# teensy-jst_01_1.net
KiCad netlist of a schematic drawn in EAGLE
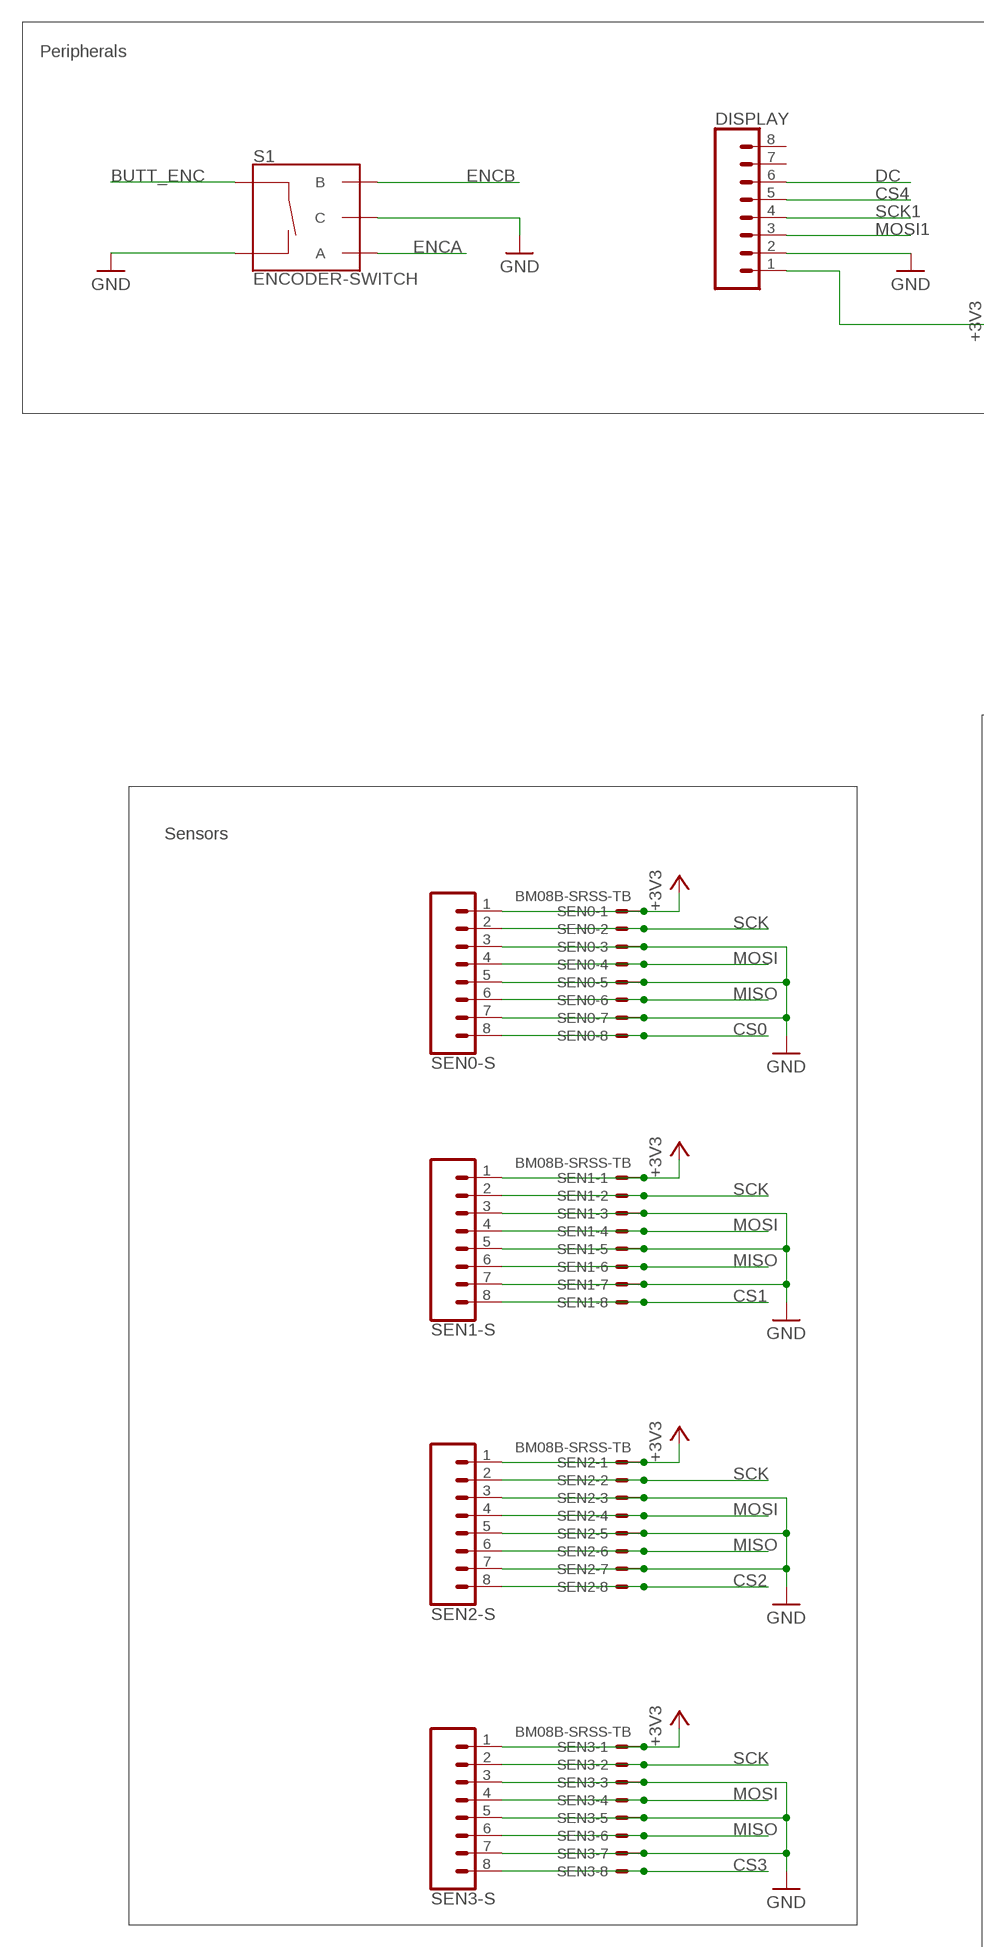
[diagram p0: schematic, sheet 1, part 1 of 2]
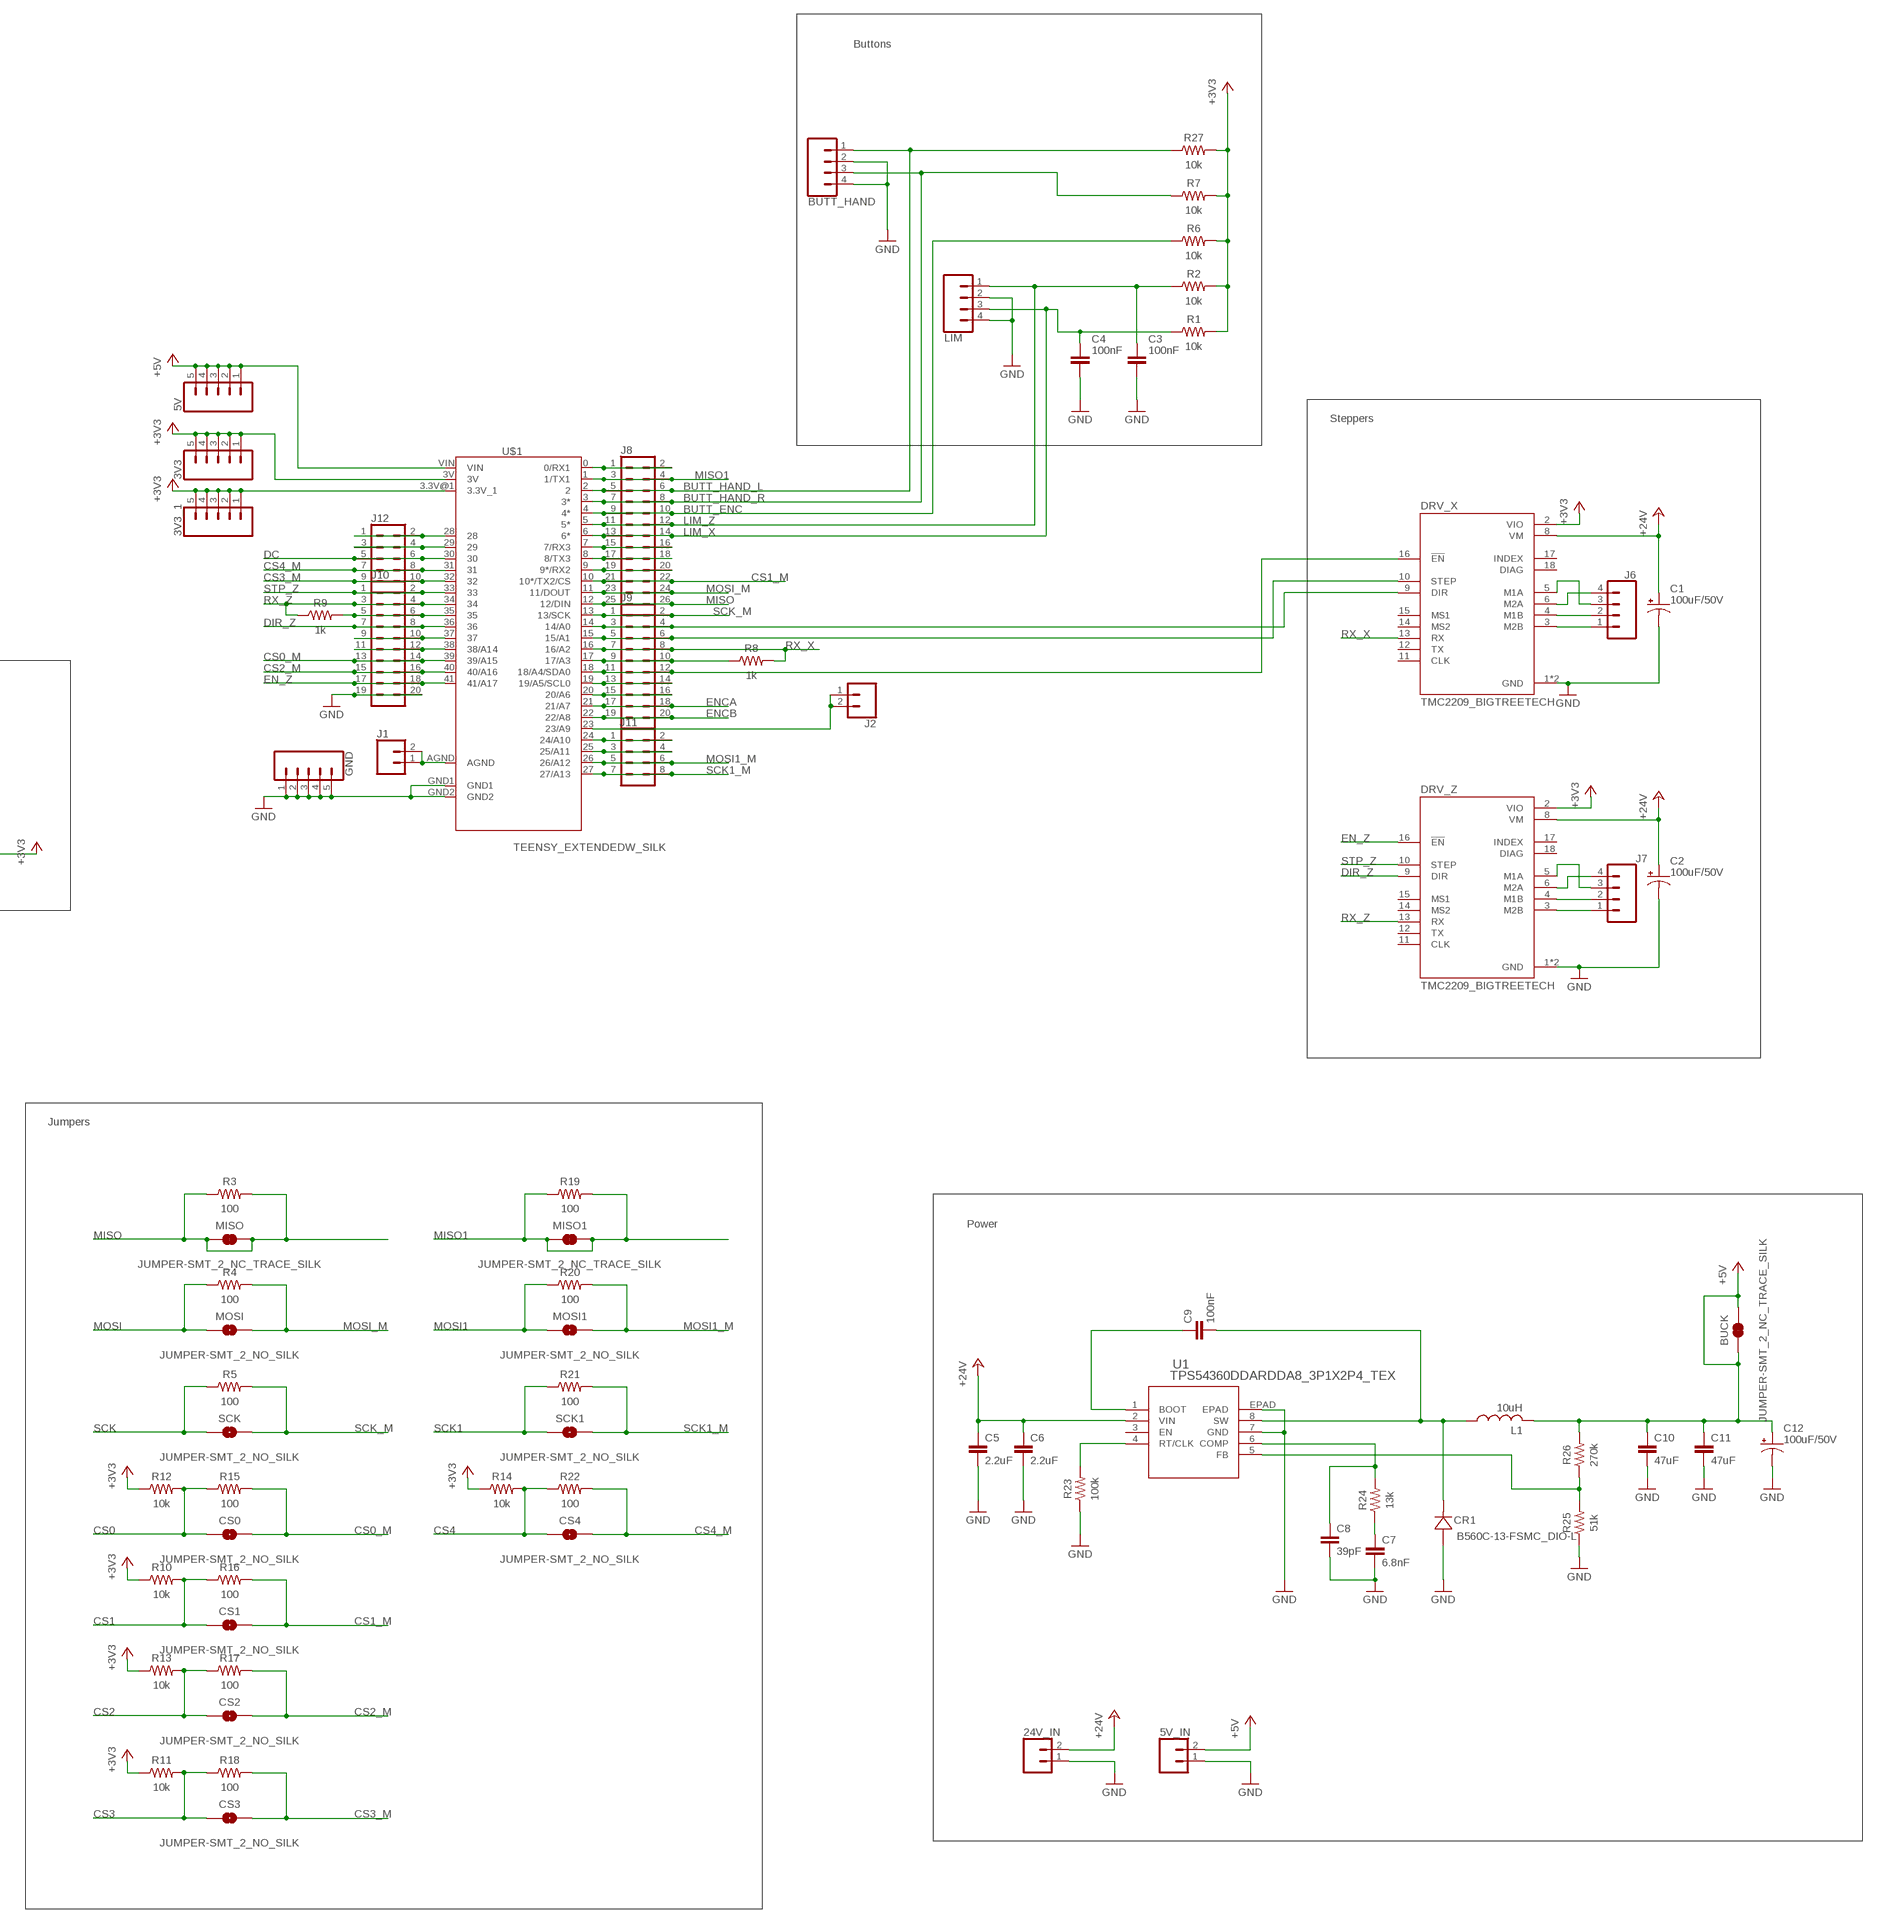
[diagram p1: schematic, sheet 1, part 2 of 2]

(export (version "E")
  (design (tool "Eeschema 10.0.6"))
  (components
    (comp (ref "3V3")
      (value "CONN_05PTH")
      (footprint "eagle-import:1X05")
      (libsource (lib "eagle-import") (part "CONN_05PTH"))
    )
    (comp (ref "3V3_1")
      (value "CONN_05PTH")
      (footprint "eagle-import:1X05")
      (libsource (lib "eagle-import") (part "CONN_05PTH"))
    )
    (comp (ref "5V")
      (value "CONN_05PTH")
      (footprint "eagle-import:1X05")
      (libsource (lib "eagle-import") (part "CONN_05PTH"))
    )
    (comp (ref "5V_IN")
      (value "CONN_025MM")
      (footprint "eagle-import:SCREWTERMINAL-5MM-2")
      (libsource (lib "eagle-import") (part "CONN_025MM"))
    )
    (comp (ref "24V_IN")
      (value "CONN_025MM")
      (footprint "eagle-import:SCREWTERMINAL-5MM-2")
      (libsource (lib "eagle-import") (part "CONN_025MM"))
    )
    (comp (ref "BUCK")
      (value "JUMPER-SMT_2_NC_TRACE_SILK")
      (footprint "eagle-import:SMT-JUMPER_2_NC_TRACE_SILK")
      (libsource (lib "eagle-import") (part "JUMPER-SMT_2_NC_TRACE_SILK"))
    )
    (comp (ref "BUTT_HAND")
      (value "CONN_041X04_NO_SILK")
      (footprint "eagle-import:1X04_NO_SILK")
      (libsource (lib "eagle-import") (part "CONN_041X04_NO_SILK"))
    )
    (comp (ref "C1")
      (value "100uF/50V")
      (footprint "eagle-import:E5-6")
      (libsource (lib "eagle-import") (part "CPOL-USE5-6"))
    )
    (comp (ref "C2")
      (value "100uF/50V")
      (footprint "eagle-import:E5-6")
      (libsource (lib "eagle-import") (part "CPOL-USE5-6"))
    )
    (comp (ref "C3")
      (value "100nF")
      (footprint "eagle-import:C0603")
      (libsource (lib "eagle-import") (part "C-EUC0603"))
    )
    (comp (ref "C4")
      (value "100nF")
      (footprint "eagle-import:C0603")
      (libsource (lib "eagle-import") (part "C-EUC0603"))
    )
    (comp (ref "C5")
      (value "2.2uF")
      (footprint "eagle-import:C0603")
      (libsource (lib "eagle-import") (part "C-EUC0603"))
    )
    (comp (ref "C6")
      (value "2.2uF")
      (footprint "eagle-import:C0603")
      (libsource (lib "eagle-import") (part "C-EUC0603"))
    )
    (comp (ref "C7")
      (value "6.8nF")
      (footprint "eagle-import:C0402")
      (libsource (lib "eagle-import") (part "C-EUC0402"))
    )
    (comp (ref "C8")
      (value "39pF")
      (footprint "eagle-import:C0402")
      (libsource (lib "eagle-import") (part "C-EUC0402"))
    )
    (comp (ref "C9")
      (value "100nF")
      (footprint "eagle-import:C0402")
      (libsource (lib "eagle-import") (part "C-EUC0402"))
    )
    (comp (ref "C10")
      (value "47uF")
      (footprint "eagle-import:C0603")
      (libsource (lib "eagle-import") (part "C-EUC0603"))
    )
    (comp (ref "C11")
      (value "47uF")
      (footprint "eagle-import:C0603")
      (libsource (lib "eagle-import") (part "C-EUC0603"))
    )
    (comp (ref "C12")
      (value "100uF/50V")
      (footprint "eagle-import:E5-6")
      (libsource (lib "eagle-import") (part "CPOL-USE5-6"))
    )
    (comp (ref "CR1")
      (value "B560C-13-FSMC_DIO-L")
      (footprint "eagle-import:SMC_DIO-L")
      (fields
        (field (name "MANUFACTURER_PART_NUMBER") "B560C-13-F")
        (field (name "COPYRIGHT") "Copyright (C) 2024 Ultra Librarian. All rights reserved.")
      )
      (libsource (lib "eagle-import") (part "B560C-13-FSMC_DIO-L"))
    )
    (comp (ref "CS0")
      (value "JUMPER-SMT_2_NO_SILK")
      (footprint "eagle-import:SMT-JUMPER_2_NO_SILK")
      (libsource (lib "eagle-import") (part "JUMPER-SMT_2_NO_SILK"))
    )
    (comp (ref "CS1")
      (value "JUMPER-SMT_2_NO_SILK")
      (footprint "eagle-import:SMT-JUMPER_2_NO_SILK")
      (libsource (lib "eagle-import") (part "JUMPER-SMT_2_NO_SILK"))
    )
    (comp (ref "CS2")
      (value "JUMPER-SMT_2_NO_SILK")
      (footprint "eagle-import:SMT-JUMPER_2_NO_SILK")
      (libsource (lib "eagle-import") (part "JUMPER-SMT_2_NO_SILK"))
    )
    (comp (ref "CS3")
      (value "JUMPER-SMT_2_NO_SILK")
      (footprint "eagle-import:SMT-JUMPER_2_NO_SILK")
      (libsource (lib "eagle-import") (part "JUMPER-SMT_2_NO_SILK"))
    )
    (comp (ref "CS4")
      (value "JUMPER-SMT_2_NO_SILK")
      (footprint "eagle-import:SMT-JUMPER_2_NO_SILK")
      (libsource (lib "eagle-import") (part "JUMPER-SMT_2_NO_SILK"))
    )
    (comp (ref "DISPLAY")
      (value "CONN_08\"")
      (footprint "eagle-import:1X08")
      (libsource (lib "eagle-import") (part "CONN_08{dblquote}"))
    )
    (comp (ref "DRV_X")
      (value "TMC2209_BIGTREETECH")
      (footprint "eagle-import:MODULE_TMC2209_BIGTREETECH")
      (fields
        (field (name "MF") "Trinamic Motion Control GmbH")
        (field (name "MP") "TMC2209 SILENTSTEPSTICK")
      )
      (libsource (lib "eagle-import") (part "TMC2209_BIGTREETECH"))
    )
    (comp (ref "DRV_Z")
      (value "TMC2209_BIGTREETECH")
      (footprint "eagle-import:MODULE_TMC2209_BIGTREETECH")
      (fields
        (field (name "MF") "Trinamic Motion Control GmbH")
        (field (name "MP") "TMC2209 SILENTSTEPSTICK")
      )
      (libsource (lib "eagle-import") (part "TMC2209_BIGTREETECH"))
    )
    (comp (ref "GND")
      (value "CONN_05PTH")
      (footprint "eagle-import:1X05")
      (libsource (lib "eagle-import") (part "CONN_05PTH"))
    )
    (comp (ref "J1")
      (value "CONN_02")
      (footprint "eagle-import:1X02")
      (libsource (lib "eagle-import") (part "CONN_02"))
    )
    (comp (ref "J2")
      (value "CONN_02")
      (footprint "eagle-import:1X02")
      (libsource (lib "eagle-import") (part "CONN_02"))
    )
    (comp (ref "J6")
      (value "CONN_04PTH")
      (footprint "eagle-import:1X04")
      (libsource (lib "eagle-import") (part "CONN_04PTH"))
    )
    (comp (ref "J7")
      (value "CONN_04PTH")
      (footprint "eagle-import:1X04")
      (libsource (lib "eagle-import") (part "CONN_04PTH"))
    )
    (comp (ref "J8")
      (value "CONN_13X22X13")
      (footprint "eagle-import:2X13")
      (libsource (lib "eagle-import") (part "CONN_13X22X13"))
    )
    (comp (ref "J9")
      (value "CONN_10X2")
      (footprint "eagle-import:2X10")
      (libsource (lib "eagle-import") (part "CONN_10X2"))
    )
    (comp (ref "J10")
      (value "CONN_10X2")
      (footprint "eagle-import:2X10")
      (libsource (lib "eagle-import") (part "CONN_10X2"))
    )
    (comp (ref "J11")
      (value "CONN_04X2")
      (footprint "eagle-import:2X4")
      (libsource (lib "eagle-import") (part "CONN_04X2"))
    )
    (comp (ref "J12")
      (value "CONN_05X2PTH")
      (footprint "eagle-import:2X5")
      (libsource (lib "eagle-import") (part "CONN_05X2PTH"))
    )
    (comp (ref "L1")
      (value "10uH")
      (footprint "eagle-import:MWSA0503S-100MT")
      (libsource (lib "eagle-import") (part "L-USMWSA0503S-100MT"))
    )
    (comp (ref "LIM")
      (value "CONN_041X04_NO_SILK")
      (footprint "eagle-import:1X04_NO_SILK")
      (libsource (lib "eagle-import") (part "CONN_041X04_NO_SILK"))
    )
    (comp (ref "MISO")
      (value "JUMPER-SMT_2_NC_TRACE_SILK")
      (footprint "eagle-import:SMT-JUMPER_2_NC_TRACE_SILK")
      (libsource (lib "eagle-import") (part "JUMPER-SMT_2_NC_TRACE_SILK"))
    )
    (comp (ref "MISO1")
      (value "JUMPER-SMT_2_NC_TRACE_SILK")
      (footprint "eagle-import:SMT-JUMPER_2_NC_TRACE_SILK")
      (libsource (lib "eagle-import") (part "JUMPER-SMT_2_NC_TRACE_SILK"))
    )
    (comp (ref "MOSI")
      (value "JUMPER-SMT_2_NO_SILK")
      (footprint "eagle-import:SMT-JUMPER_2_NO_SILK")
      (libsource (lib "eagle-import") (part "JUMPER-SMT_2_NO_SILK"))
    )
    (comp (ref "MOSI1")
      (value "JUMPER-SMT_2_NO_SILK")
      (footprint "eagle-import:SMT-JUMPER_2_NO_SILK")
      (libsource (lib "eagle-import") (part "JUMPER-SMT_2_NO_SILK"))
    )
    (comp (ref "R1")
      (value "10k")
      (footprint "eagle-import:RESC1608X60")
      (libsource (lib "eagle-import") (part "R-USCHIP-0603(1608-METRIC)_"))
    )
    (comp (ref "R2")
      (value "10k")
      (footprint "eagle-import:RESC1608X60")
      (libsource (lib "eagle-import") (part "R-USCHIP-0603(1608-METRIC)_"))
    )
    (comp (ref "R3")
      (value "100")
      (footprint "eagle-import:RESC1608X60")
      (libsource (lib "eagle-import") (part "R-USCHIP-0603(1608-METRIC)_"))
    )
    (comp (ref "R4")
      (value "100")
      (footprint "eagle-import:RESC1608X60")
      (libsource (lib "eagle-import") (part "R-USCHIP-0603(1608-METRIC)_"))
    )
    (comp (ref "R5")
      (value "100")
      (footprint "eagle-import:RESC1608X60")
      (libsource (lib "eagle-import") (part "R-USCHIP-0603(1608-METRIC)_"))
    )
    (comp (ref "R6")
      (value "10k")
      (footprint "eagle-import:RESC1608X60")
      (libsource (lib "eagle-import") (part "R-USCHIP-0603(1608-METRIC)_"))
    )
    (comp (ref "R7")
      (value "10k")
      (footprint "eagle-import:RESC1608X60")
      (libsource (lib "eagle-import") (part "R-USCHIP-0603(1608-METRIC)_"))
    )
    (comp (ref "R8")
      (value "1k")
      (footprint "eagle-import:RESC1608X60")
      (libsource (lib "eagle-import") (part "R-USCHIP-0603(1608-METRIC)_"))
    )
    (comp (ref "R9")
      (value "1k")
      (footprint "eagle-import:RESC1608X60")
      (libsource (lib "eagle-import") (part "R-USCHIP-0603(1608-METRIC)_"))
    )
    (comp (ref "R10")
      (value "10k")
      (footprint "eagle-import:RESC1608X60")
      (libsource (lib "eagle-import") (part "R-USCHIP-0603(1608-METRIC)_"))
    )
    (comp (ref "R11")
      (value "10k")
      (footprint "eagle-import:RESC1608X60")
      (libsource (lib "eagle-import") (part "R-USCHIP-0603(1608-METRIC)_"))
    )
    (comp (ref "R12")
      (value "10k")
      (footprint "eagle-import:RESC1608X60")
      (libsource (lib "eagle-import") (part "R-USCHIP-0603(1608-METRIC)_"))
    )
    (comp (ref "R13")
      (value "10k")
      (footprint "eagle-import:RESC1608X60")
      (libsource (lib "eagle-import") (part "R-USCHIP-0603(1608-METRIC)_"))
    )
    (comp (ref "R14")
      (value "10k")
      (footprint "eagle-import:RESC1608X60")
      (libsource (lib "eagle-import") (part "R-USCHIP-0603(1608-METRIC)_"))
    )
    (comp (ref "R15")
      (value "100")
      (footprint "eagle-import:RESC1608X60")
      (libsource (lib "eagle-import") (part "R-USCHIP-0603(1608-METRIC)_"))
    )
    (comp (ref "R16")
      (value "100")
      (footprint "eagle-import:RESC1608X60")
      (libsource (lib "eagle-import") (part "R-USCHIP-0603(1608-METRIC)_"))
    )
    (comp (ref "R17")
      (value "100")
      (footprint "eagle-import:RESC1608X60")
      (libsource (lib "eagle-import") (part "R-USCHIP-0603(1608-METRIC)_"))
    )
    (comp (ref "R18")
      (value "100")
      (footprint "eagle-import:RESC1608X60")
      (libsource (lib "eagle-import") (part "R-USCHIP-0603(1608-METRIC)_"))
    )
    (comp (ref "R19")
      (value "100")
      (footprint "eagle-import:RESC1608X60")
      (libsource (lib "eagle-import") (part "R-USCHIP-0603(1608-METRIC)_"))
    )
    (comp (ref "R20")
      (value "100")
      (footprint "eagle-import:RESC1608X60")
      (libsource (lib "eagle-import") (part "R-USCHIP-0603(1608-METRIC)_"))
    )
    (comp (ref "R21")
      (value "100")
      (footprint "eagle-import:RESC1608X60")
      (libsource (lib "eagle-import") (part "R-USCHIP-0603(1608-METRIC)_"))
    )
    (comp (ref "R22")
      (value "100")
      (footprint "eagle-import:RESC1608X60")
      (libsource (lib "eagle-import") (part "R-USCHIP-0603(1608-METRIC)_"))
    )
    (comp (ref "R23")
      (value "100k")
      (footprint "eagle-import:RESC1005X40")
      (libsource (lib "eagle-import") (part "R-USCHIP-0402(1005-METRIC)_"))
    )
    (comp (ref "R24")
      (value "13k")
      (footprint "eagle-import:RESC1005X40")
      (libsource (lib "eagle-import") (part "R-USCHIP-0402(1005-METRIC)_"))
    )
    (comp (ref "R25")
      (value "51k")
      (footprint "eagle-import:RESC1005X40")
      (libsource (lib "eagle-import") (part "R-USCHIP-0402(1005-METRIC)_"))
    )
    (comp (ref "R26")
      (value "270k")
      (footprint "eagle-import:RESC1005X40")
      (libsource (lib "eagle-import") (part "R-USCHIP-0402(1005-METRIC)_"))
    )
    (comp (ref "R27")
      (value "10k")
      (footprint "eagle-import:RESC1608X60")
      (libsource (lib "eagle-import") (part "R-USCHIP-0603(1608-METRIC)_"))
    )
    (comp (ref "S1")
      (value "ENCODER-SWITCH")
      (footprint "eagle-import:ROTARY_ENC_PLAIN")
      (libsource (lib "eagle-import") (part "ENCODER-SWITCH"))
    )
    (comp (ref "SCK")
      (value "JUMPER-SMT_2_NO_SILK")
      (footprint "eagle-import:SMT-JUMPER_2_NO_SILK")
      (libsource (lib "eagle-import") (part "JUMPER-SMT_2_NO_SILK"))
    )
    (comp (ref "SCK1")
      (value "JUMPER-SMT_2_NO_SILK")
      (footprint "eagle-import:SMT-JUMPER_2_NO_SILK")
      (libsource (lib "eagle-import") (part "JUMPER-SMT_2_NO_SILK"))
    )
    (comp (ref "SEN0")
      (value "BM08B-SRSS-TB")
      (footprint "eagle-import:BM08B-SRSS-TB")
      (libsource (lib "eagle-import") (part "?M08B-SRSS-TBB"))
    )
    (comp (ref "SEN0-S")
      (value "CONN_08\"")
      (footprint "eagle-import:1X08")
      (libsource (lib "eagle-import") (part "CONN_08{dblquote}"))
    )
    (comp (ref "SEN1")
      (value "BM08B-SRSS-TB")
      (footprint "eagle-import:BM08B-SRSS-TB")
      (libsource (lib "eagle-import") (part "?M08B-SRSS-TBB"))
    )
    (comp (ref "SEN1-S")
      (value "CONN_08\"")
      (footprint "eagle-import:1X08")
      (libsource (lib "eagle-import") (part "CONN_08{dblquote}"))
    )
    (comp (ref "SEN2")
      (value "BM08B-SRSS-TB")
      (footprint "eagle-import:BM08B-SRSS-TB")
      (libsource (lib "eagle-import") (part "?M08B-SRSS-TBB"))
    )
    (comp (ref "SEN2-S")
      (value "CONN_08\"")
      (footprint "eagle-import:1X08")
      (libsource (lib "eagle-import") (part "CONN_08{dblquote}"))
    )
    (comp (ref "SEN3")
      (value "BM08B-SRSS-TB")
      (footprint "eagle-import:BM08B-SRSS-TB")
      (libsource (lib "eagle-import") (part "?M08B-SRSS-TBB"))
    )
    (comp (ref "SEN3-S")
      (value "CONN_08\"")
      (footprint "eagle-import:1X08")
      (libsource (lib "eagle-import") (part "CONN_08{dblquote}"))
    )
    (comp (ref "U$1")
      (value "TEENSY_EXTENDEDW_SILK")
      (footprint "eagle-import:TEENSY_EXTENDED")
      (libsource (lib "eagle-import") (part "TEENSY_EXTENDEDW_SILK"))
    )
    (comp (ref "U1")
      (value "TPS54360DDARDDA8_3P1X2P4_TEX")
      (footprint "eagle-import:DDA8_3P1X2P4_TEX")
      (fields
        (field (name "MANUFACTURER_PART_NUMBER") "TPS54360DDAR")
        (field (name "COPYRIGHT") "Copyright (C) 2024 Ultra Librarian. All rights reserved.")
      )
      (libsource (lib "eagle-import") (part "TPS54360DDARDDA8_3P1X2P4_TEX"))
    )
  )
  (nets
    (net (code "1") (name "+3V3") (class "Default")
      (node (ref "3V3") (pin "1") (pinfunction "1_1") (pintype "passive"))
      (node (ref "3V3") (pin "2") (pinfunction "2_2") (pintype "passive"))
      (node (ref "3V3") (pin "3") (pinfunction "3_3") (pintype "passive"))
      (node (ref "3V3") (pin "4") (pinfunction "4_4") (pintype "passive"))
      (node (ref "3V3") (pin "5") (pinfunction "5_5") (pintype "passive"))
      (node (ref "3V3_1") (pin "1") (pinfunction "1_1") (pintype "passive"))
      (node (ref "3V3_1") (pin "2") (pinfunction "2_2") (pintype "passive"))
      (node (ref "3V3_1") (pin "3") (pinfunction "3_3") (pintype "passive"))
      (node (ref "3V3_1") (pin "4") (pinfunction "4_4") (pintype "passive"))
      (node (ref "3V3_1") (pin "5") (pinfunction "5_5") (pintype "passive"))
      (node (ref "DISPLAY") (pin "1") (pinfunction "1_1") (pintype "passive"))
      (node (ref "DRV_X") (pin "2") (pinfunction "VIO_2") (pintype "power_in"))
      (node (ref "DRV_Z") (pin "2") (pinfunction "VIO_2") (pintype "power_in"))
      (node (ref "R1") (pin "2") (pinfunction "2_2") (pintype "passive"))
      (node (ref "R10") (pin "1") (pinfunction "1_1") (pintype "passive"))
      (node (ref "R11") (pin "1") (pinfunction "1_1") (pintype "passive"))
      (node (ref "R12") (pin "1") (pinfunction "1_1") (pintype "passive"))
      (node (ref "R13") (pin "1") (pinfunction "1_1") (pintype "passive"))
      (node (ref "R14") (pin "1") (pinfunction "1_1") (pintype "passive"))
      (node (ref "R2") (pin "2") (pinfunction "2_2") (pintype "passive"))
      (node (ref "R27") (pin "2") (pinfunction "2_2") (pintype "passive"))
      (node (ref "R6") (pin "2") (pinfunction "2_2") (pintype "passive"))
      (node (ref "R7") (pin "2") (pinfunction "2_2") (pintype "passive"))
      (node (ref "SEN0") (pin "1") (pinfunction "S_1") (pintype "passive"))
      (node (ref "SEN0-S") (pin "1") (pinfunction "1_1") (pintype "passive"))
      (node (ref "SEN1") (pin "1") (pinfunction "S_1") (pintype "passive"))
      (node (ref "SEN1-S") (pin "1") (pinfunction "1_1") (pintype "passive"))
      (node (ref "SEN2") (pin "1") (pinfunction "S_1") (pintype "passive"))
      (node (ref "SEN2-S") (pin "1") (pinfunction "1_1") (pintype "passive"))
      (node (ref "SEN3") (pin "1") (pinfunction "S_1") (pintype "passive"))
      (node (ref "SEN3-S") (pin "1") (pinfunction "1_1") (pintype "passive"))
      (node (ref "U$1") (pin "3.3V@1") (pinfunction "3.3V_1_3.3V@1") (pintype "power_in"))
      (node (ref "U$1") (pin "3V") (pinfunction "3V_3V") (pintype "power_in"))
    )
    (net (code "2") (name "+5V") (class "Default")
      (node (ref "5V") (pin "1") (pinfunction "1_1") (pintype "passive"))
      (node (ref "5V") (pin "2") (pinfunction "2_2") (pintype "passive"))
      (node (ref "5V") (pin "3") (pinfunction "3_3") (pintype "passive"))
      (node (ref "5V") (pin "4") (pinfunction "4_4") (pintype "passive"))
      (node (ref "5V") (pin "5") (pinfunction "5_5") (pintype "passive"))
      (node (ref "5V_IN") (pin "2") (pinfunction "2_2") (pintype "passive"))
      (node (ref "BUCK") (pin "1") (pinfunction "1_1") (pintype "passive"))
      (node (ref "BUCK") (pin "2") (pinfunction "2_2") (pintype "passive"))
      (node (ref "C10") (pin "1") (pinfunction "1_1") (pintype "passive"))
      (node (ref "C11") (pin "1") (pinfunction "1_1") (pintype "passive"))
      (node (ref "C12") (pin "+") (pinfunction "+_+") (pintype "passive"))
      (node (ref "L1") (pin "2") (pinfunction "2_2") (pintype "passive"))
      (node (ref "R26") (pin "2") (pinfunction "2_2") (pintype "passive"))
      (node (ref "U$1") (pin "VIN") (pinfunction "VIN_VIN") (pintype "power_in"))
    )
    (net (code "3") (name "+24V") (class "Default")
      (node (ref "24V_IN") (pin "2") (pinfunction "2_2") (pintype "passive"))
      (node (ref "C1") (pin "+") (pinfunction "+_+") (pintype "passive"))
      (node (ref "C2") (pin "+") (pinfunction "+_+") (pintype "passive"))
      (node (ref "C5") (pin "1") (pinfunction "1_1") (pintype "passive"))
      (node (ref "C6") (pin "1") (pinfunction "1_1") (pintype "passive"))
      (node (ref "DRV_X") (pin "8") (pinfunction "VM_8") (pintype "power_in"))
      (node (ref "DRV_Z") (pin "8") (pinfunction "VM_8") (pintype "power_in"))
      (node (ref "U1") (pin "2") (pinfunction "VIN_2") (pintype "input"))
    )
    (net (code "4") (name "/BUTT_ENC") (class "Default")
      (node (ref "J8") (pin "10") (pinfunction "10_10") (pintype "passive"))
      (node (ref "J8") (pin "9") (pinfunction "9_9") (pintype "passive"))
      (node (ref "R6") (pin "1") (pinfunction "1_1") (pintype "passive"))
      (node (ref "S1") (pin "SW+") (pinfunction "SW+_SW+") (pintype "bidirectional"))
      (node (ref "U$1") (pin "4") (pinfunction "4*_4") (pintype "bidirectional"))
    )
    (net (code "5") (name "/BUTT_HAND_L") (class "Default")
      (node (ref "BUTT_HAND") (pin "1") (pinfunction "1_1") (pintype "passive"))
      (node (ref "J8") (pin "5") (pinfunction "5_5") (pintype "passive"))
      (node (ref "J8") (pin "6") (pinfunction "6_6") (pintype "passive"))
      (node (ref "R27") (pin "1") (pinfunction "1_1") (pintype "passive"))
      (node (ref "U$1") (pin "2") (pinfunction "2_2") (pintype "bidirectional"))
    )
    (net (code "6") (name "/BUTT_HAND_R") (class "Default")
      (node (ref "BUTT_HAND") (pin "3") (pinfunction "3_3") (pintype "passive"))
      (node (ref "J8") (pin "7") (pinfunction "7_7") (pintype "passive"))
      (node (ref "J8") (pin "8") (pinfunction "8_8") (pintype "passive"))
      (node (ref "R7") (pin "1") (pinfunction "1_1") (pintype "passive"))
      (node (ref "U$1") (pin "3") (pinfunction "3*_3") (pintype "bidirectional"))
    )
    (net (code "7") (name "/CS0") (class "Default")
      (node (ref "CS0") (pin "1") (pinfunction "1_1") (pintype "passive"))
      (node (ref "R12") (pin "2") (pinfunction "2_2") (pintype "passive"))
      (node (ref "R15") (pin "1") (pinfunction "1_1") (pintype "passive"))
      (node (ref "SEN0") (pin "8") (pinfunction "S_8") (pintype "passive"))
      (node (ref "SEN0-S") (pin "8") (pinfunction "8_8") (pintype "passive"))
    )
    (net (code "8") (name "/CS0_M") (class "Default")
      (node (ref "CS0") (pin "2") (pinfunction "2_2") (pintype "passive"))
      (node (ref "J10") (pin "13") (pinfunction "13_13") (pintype "passive"))
      (node (ref "J10") (pin "14") (pinfunction "14_14") (pintype "passive"))
      (node (ref "R15") (pin "2") (pinfunction "2_2") (pintype "passive"))
      (node (ref "U$1") (pin "39") (pinfunction "39/A15_39") (pintype "bidirectional"))
    )
    (net (code "9") (name "/CS1") (class "Default")
      (node (ref "CS1") (pin "1") (pinfunction "1_1") (pintype "passive"))
      (node (ref "R10") (pin "2") (pinfunction "2_2") (pintype "passive"))
      (node (ref "R16") (pin "1") (pinfunction "1_1") (pintype "passive"))
      (node (ref "SEN1") (pin "8") (pinfunction "S_8") (pintype "passive"))
      (node (ref "SEN1-S") (pin "8") (pinfunction "8_8") (pintype "passive"))
    )
    (net (code "10") (name "/CS1_M") (class "Default")
      (node (ref "CS1") (pin "2") (pinfunction "2_2") (pintype "passive"))
      (node (ref "J8") (pin "21") (pinfunction "21_21") (pintype "passive"))
      (node (ref "J8") (pin "22") (pinfunction "22_22") (pintype "passive"))
      (node (ref "R16") (pin "2") (pinfunction "2_2") (pintype "passive"))
      (node (ref "U$1") (pin "10") (pinfunction "10*/TX2/CS_10") (pintype "bidirectional"))
    )
    (net (code "11") (name "/CS2") (class "Default")
      (node (ref "CS2") (pin "1") (pinfunction "1_1") (pintype "passive"))
      (node (ref "R13") (pin "2") (pinfunction "2_2") (pintype "passive"))
      (node (ref "R17") (pin "1") (pinfunction "1_1") (pintype "passive"))
      (node (ref "SEN2") (pin "8") (pinfunction "S_8") (pintype "passive"))
      (node (ref "SEN2-S") (pin "8") (pinfunction "8_8") (pintype "passive"))
    )
    (net (code "12") (name "/CS2_M") (class "Default")
      (node (ref "CS2") (pin "2") (pinfunction "2_2") (pintype "passive"))
      (node (ref "J10") (pin "15") (pinfunction "15_15") (pintype "passive"))
      (node (ref "J10") (pin "16") (pinfunction "16_16") (pintype "passive"))
      (node (ref "R17") (pin "2") (pinfunction "2_2") (pintype "passive"))
      (node (ref "U$1") (pin "40") (pinfunction "40/A16_40") (pintype "bidirectional"))
    )
    (net (code "13") (name "/CS3") (class "Default")
      (node (ref "CS3") (pin "1") (pinfunction "1_1") (pintype "passive"))
      (node (ref "R11") (pin "2") (pinfunction "2_2") (pintype "passive"))
      (node (ref "R18") (pin "1") (pinfunction "1_1") (pintype "passive"))
      (node (ref "SEN3") (pin "8") (pinfunction "S_8") (pintype "passive"))
      (node (ref "SEN3-S") (pin "8") (pinfunction "8_8") (pintype "passive"))
    )
    (net (code "14") (name "/CS3_M") (class "Default")
      (node (ref "CS3") (pin "2") (pinfunction "2_2") (pintype "passive"))
      (node (ref "J12") (pin "10") (pinfunction "10_10") (pintype "passive"))
      (node (ref "J12") (pin "9") (pinfunction "9_9") (pintype "passive"))
      (node (ref "R18") (pin "2") (pinfunction "2_2") (pintype "passive"))
      (node (ref "U$1") (pin "32") (pinfunction "32_32") (pintype "bidirectional"))
    )
    (net (code "15") (name "/CS4") (class "Default")
      (node (ref "CS4") (pin "1") (pinfunction "1_1") (pintype "passive"))
      (node (ref "DISPLAY") (pin "5") (pinfunction "5_5") (pintype "passive"))
      (node (ref "R14") (pin "2") (pinfunction "2_2") (pintype "passive"))
      (node (ref "R22") (pin "1") (pinfunction "1_1") (pintype "passive"))
    )
    (net (code "16") (name "/CS4_M") (class "Default")
      (node (ref "CS4") (pin "2") (pinfunction "2_2") (pintype "passive"))
      (node (ref "J12") (pin "7") (pinfunction "7_7") (pintype "passive"))
      (node (ref "J12") (pin "8") (pinfunction "8_8") (pintype "passive"))
      (node (ref "R22") (pin "2") (pinfunction "2_2") (pintype "passive"))
      (node (ref "U$1") (pin "31") (pinfunction "31_31") (pintype "bidirectional"))
    )
    (net (code "17") (name "/DC") (class "Default")
      (node (ref "DISPLAY") (pin "6") (pinfunction "6_6") (pintype "passive"))
      (node (ref "J12") (pin "5") (pinfunction "5_5") (pintype "passive"))
      (node (ref "J12") (pin "6") (pinfunction "6_6") (pintype "passive"))
      (node (ref "U$1") (pin "30") (pinfunction "30_30") (pintype "bidirectional"))
    )
    (net (code "18") (name "/DIR_Z") (class "Default")
      (node (ref "DRV_Z") (pin "9") (pinfunction "DIR_9") (pintype "input"))
      (node (ref "J10") (pin "7") (pinfunction "7_7") (pintype "passive"))
      (node (ref "J10") (pin "8") (pinfunction "8_8") (pintype "passive"))
      (node (ref "U$1") (pin "36") (pinfunction "36_36") (pintype "bidirectional"))
    )
    (net (code "19") (name "/ENCA") (class "Default")
      (node (ref "J9") (pin "17") (pinfunction "17_17") (pintype "passive"))
      (node (ref "J9") (pin "18") (pinfunction "18_18") (pintype "passive"))
      (node (ref "S1") (pin "A") (pinfunction "A_A") (pintype "bidirectional"))
      (node (ref "U$1") (pin "21") (pinfunction "21/A7_21") (pintype "bidirectional"))
    )
    (net (code "20") (name "/ENCB") (class "Default")
      (node (ref "J9") (pin "19") (pinfunction "19_19") (pintype "passive"))
      (node (ref "J9") (pin "20") (pinfunction "20_20") (pintype "passive"))
      (node (ref "S1") (pin "B") (pinfunction "B_B") (pintype "bidirectional"))
      (node (ref "U$1") (pin "22") (pinfunction "22/A8_22") (pintype "bidirectional"))
    )
    (net (code "21") (name "/EN_Z") (class "Default")
      (node (ref "DRV_Z") (pin "16") (pinfunction "~{EN}_16") (pintype "input"))
      (node (ref "J10") (pin "17") (pinfunction "17_17") (pintype "passive"))
      (node (ref "J10") (pin "18") (pinfunction "18_18") (pintype "passive"))
      (node (ref "U$1") (pin "41") (pinfunction "41/A17_41") (pintype "bidirectional"))
    )
    (net (code "22") (name "/LIM_X") (class "Default")
      (node (ref "C4") (pin "1") (pinfunction "1_1") (pintype "passive"))
      (node (ref "J8") (pin "13") (pinfunction "13_13") (pintype "passive"))
      (node (ref "J8") (pin "14") (pinfunction "14_14") (pintype "passive"))
      (node (ref "LIM") (pin "3") (pinfunction "3_3") (pintype "passive"))
      (node (ref "R1") (pin "1") (pinfunction "1_1") (pintype "passive"))
      (node (ref "U$1") (pin "6") (pinfunction "6*_6") (pintype "bidirectional"))
    )
    (net (code "23") (name "/LIM_Z") (class "Default")
      (node (ref "C3") (pin "1") (pinfunction "1_1") (pintype "passive"))
      (node (ref "J8") (pin "11") (pinfunction "11_11") (pintype "passive"))
      (node (ref "J8") (pin "12") (pinfunction "12_12") (pintype "passive"))
      (node (ref "LIM") (pin "1") (pinfunction "1_1") (pintype "passive"))
      (node (ref "R2") (pin "1") (pinfunction "1_1") (pintype "passive"))
      (node (ref "U$1") (pin "5") (pinfunction "5*_5") (pintype "bidirectional"))
    )
    (net (code "24") (name "/MISO") (class "Default")
      (node (ref "J8") (pin "25") (pinfunction "25_25") (pintype "passive"))
      (node (ref "J8") (pin "26") (pinfunction "26_26") (pintype "passive"))
      (node (ref "MISO") (pin "1") (pinfunction "1_1") (pintype "passive"))
      (node (ref "MISO") (pin "2") (pinfunction "2_2") (pintype "passive"))
      (node (ref "R3") (pin "1") (pinfunction "1_1") (pintype "passive"))
      (node (ref "R3") (pin "2") (pinfunction "2_2") (pintype "passive"))
      (node (ref "SEN0") (pin "6") (pinfunction "S_6") (pintype "passive"))
      (node (ref "SEN0-S") (pin "6") (pinfunction "6_6") (pintype "passive"))
      (node (ref "SEN1") (pin "6") (pinfunction "S_6") (pintype "passive"))
      (node (ref "SEN1-S") (pin "6") (pinfunction "6_6") (pintype "passive"))
      (node (ref "SEN2") (pin "6") (pinfunction "S_6") (pintype "passive"))
      (node (ref "SEN2-S") (pin "6") (pinfunction "6_6") (pintype "passive"))
      (node (ref "SEN3") (pin "6") (pinfunction "S_6") (pintype "passive"))
      (node (ref "SEN3-S") (pin "6") (pinfunction "6_6") (pintype "passive"))
      (node (ref "U$1") (pin "12") (pinfunction "12/DIN_12") (pintype "bidirectional"))
    )
    (net (code "25") (name "/MISO1") (class "Default")
      (node (ref "J8") (pin "3") (pinfunction "3_3") (pintype "passive"))
      (node (ref "J8") (pin "4") (pinfunction "4_4") (pintype "passive"))
      (node (ref "MISO1") (pin "1") (pinfunction "1_1") (pintype "passive"))
      (node (ref "MISO1") (pin "2") (pinfunction "2_2") (pintype "passive"))
      (node (ref "R19") (pin "1") (pinfunction "1_1") (pintype "passive"))
      (node (ref "R19") (pin "2") (pinfunction "2_2") (pintype "passive"))
      (node (ref "U$1") (pin "1") (pinfunction "1/TX1_1") (pintype "bidirectional"))
    )
    (net (code "26") (name "/MOSI") (class "Default")
      (node (ref "MOSI") (pin "1") (pinfunction "1_1") (pintype "passive"))
      (node (ref "R4") (pin "1") (pinfunction "1_1") (pintype "passive"))
      (node (ref "SEN0") (pin "4") (pinfunction "S_4") (pintype "passive"))
      (node (ref "SEN0-S") (pin "4") (pinfunction "4_4") (pintype "passive"))
      (node (ref "SEN1") (pin "4") (pinfunction "S_4") (pintype "passive"))
      (node (ref "SEN1-S") (pin "4") (pinfunction "4_4") (pintype "passive"))
      (node (ref "SEN2") (pin "4") (pinfunction "S_4") (pintype "passive"))
      (node (ref "SEN2-S") (pin "4") (pinfunction "4_4") (pintype "passive"))
      (node (ref "SEN3") (pin "4") (pinfunction "S_4") (pintype "passive"))
      (node (ref "SEN3-S") (pin "4") (pinfunction "4_4") (pintype "passive"))
    )
    (net (code "27") (name "/MOSI1") (class "Default")
      (node (ref "DISPLAY") (pin "3") (pinfunction "3_3") (pintype "passive"))
      (node (ref "MOSI1") (pin "1") (pinfunction "1_1") (pintype "passive"))
      (node (ref "R20") (pin "1") (pinfunction "1_1") (pintype "passive"))
    )
    (net (code "28") (name "/MOSI1_M") (class "Default")
      (node (ref "J11") (pin "5") (pinfunction "5_5") (pintype "passive"))
      (node (ref "J11") (pin "6") (pinfunction "6_6") (pintype "passive"))
      (node (ref "MOSI1") (pin "2") (pinfunction "2_2") (pintype "passive"))
      (node (ref "R20") (pin "2") (pinfunction "2_2") (pintype "passive"))
      (node (ref "U$1") (pin "26") (pinfunction "26/A12_26") (pintype "bidirectional"))
    )
    (net (code "29") (name "/MOSI_M") (class "Default")
      (node (ref "J8") (pin "23") (pinfunction "23_23") (pintype "passive"))
      (node (ref "J8") (pin "24") (pinfunction "24_24") (pintype "passive"))
      (node (ref "MOSI") (pin "2") (pinfunction "2_2") (pintype "passive"))
      (node (ref "R4") (pin "2") (pinfunction "2_2") (pintype "passive"))
      (node (ref "U$1") (pin "11") (pinfunction "11/DOUT_11") (pintype "bidirectional"))
    )
    (net (code "30") (name "/RX_X") (class "Default")
      (node (ref "DRV_X") (pin "13") (pinfunction "RX_13") (pintype "input"))
      (node (ref "J9") (pin "7") (pinfunction "7_7") (pintype "passive"))
      (node (ref "J9") (pin "8") (pinfunction "8_8") (pintype "passive"))
      (node (ref "R8") (pin "2") (pinfunction "2_2") (pintype "passive"))
      (node (ref "U$1") (pin "16") (pinfunction "16/A2_16") (pintype "bidirectional"))
    )
    (net (code "31") (name "/RX_Z") (class "Default")
      (node (ref "DRV_Z") (pin "13") (pinfunction "RX_13") (pintype "input"))
      (node (ref "J10") (pin "3") (pinfunction "3_3") (pintype "passive"))
      (node (ref "J10") (pin "4") (pinfunction "4_4") (pintype "passive"))
      (node (ref "R9") (pin "1") (pinfunction "1_1") (pintype "passive"))
      (node (ref "U$1") (pin "34") (pinfunction "34_34") (pintype "bidirectional"))
    )
    (net (code "32") (name "/SCK") (class "Default")
      (node (ref "R5") (pin "1") (pinfunction "1_1") (pintype "passive"))
      (node (ref "SCK") (pin "1") (pinfunction "1_1") (pintype "passive"))
      (node (ref "SEN0") (pin "2") (pinfunction "S_2") (pintype "passive"))
      (node (ref "SEN0-S") (pin "2") (pinfunction "2_2") (pintype "passive"))
      (node (ref "SEN1") (pin "2") (pinfunction "S_2") (pintype "passive"))
      (node (ref "SEN1-S") (pin "2") (pinfunction "2_2") (pintype "passive"))
      (node (ref "SEN2") (pin "2") (pinfunction "S_2") (pintype "passive"))
      (node (ref "SEN2-S") (pin "2") (pinfunction "2_2") (pintype "passive"))
      (node (ref "SEN3") (pin "2") (pinfunction "S_2") (pintype "passive"))
      (node (ref "SEN3-S") (pin "2") (pinfunction "2_2") (pintype "passive"))
    )
    (net (code "33") (name "/SCK1") (class "Default")
      (node (ref "DISPLAY") (pin "4") (pinfunction "4_4") (pintype "passive"))
      (node (ref "R21") (pin "1") (pinfunction "1_1") (pintype "passive"))
      (node (ref "SCK1") (pin "1") (pinfunction "1_1") (pintype "passive"))
    )
    (net (code "34") (name "/SCK1_M") (class "Default")
      (node (ref "J11") (pin "7") (pinfunction "7_7") (pintype "passive"))
      (node (ref "J11") (pin "8") (pinfunction "8_8") (pintype "passive"))
      (node (ref "R21") (pin "2") (pinfunction "2_2") (pintype "passive"))
      (node (ref "SCK1") (pin "2") (pinfunction "2_2") (pintype "passive"))
      (node (ref "U$1") (pin "27") (pinfunction "27/A13_27") (pintype "bidirectional"))
    )
    (net (code "35") (name "/SCK_M") (class "Default")
      (node (ref "J9") (pin "1") (pinfunction "1_1") (pintype "passive"))
      (node (ref "J9") (pin "2") (pinfunction "2_2") (pintype "passive"))
      (node (ref "R5") (pin "2") (pinfunction "2_2") (pintype "passive"))
      (node (ref "SCK") (pin "2") (pinfunction "2_2") (pintype "passive"))
      (node (ref "U$1") (pin "13") (pinfunction "13/SCK_13") (pintype "bidirectional"))
    )
    (net (code "36") (name "/STP_Z") (class "Default")
      (node (ref "DRV_Z") (pin "10") (pinfunction "STEP_10") (pintype "input"))
      (node (ref "J10") (pin "1") (pinfunction "1_1") (pintype "passive"))
      (node (ref "J10") (pin "2") (pinfunction "2_2") (pintype "passive"))
      (node (ref "U$1") (pin "33") (pinfunction "33_33") (pintype "bidirectional"))
    )
    (net (code "37") (name "GND") (class "Default")
      (node (ref "24V_IN") (pin "1") (pinfunction "1_1") (pintype "passive"))
      (node (ref "5V_IN") (pin "1") (pinfunction "1_1") (pintype "passive"))
      (node (ref "BUTT_HAND") (pin "2") (pinfunction "2_2") (pintype "passive"))
      (node (ref "BUTT_HAND") (pin "4") (pinfunction "4_4") (pintype "passive"))
      (node (ref "C1") (pin "-") (pinfunction "-_-") (pintype "passive"))
      (node (ref "C10") (pin "2") (pinfunction "2_2") (pintype "passive"))
      (node (ref "C11") (pin "2") (pinfunction "2_2") (pintype "passive"))
      (node (ref "C12") (pin "-") (pinfunction "-_-") (pintype "passive"))
      (node (ref "C2") (pin "-") (pinfunction "-_-") (pintype "passive"))
      (node (ref "C3") (pin "2") (pinfunction "2_2") (pintype "passive"))
      (node (ref "C4") (pin "2") (pinfunction "2_2") (pintype "passive"))
      (node (ref "C5") (pin "2") (pinfunction "2_2") (pintype "passive"))
      (node (ref "C6") (pin "2") (pinfunction "2_2") (pintype "passive"))
      (node (ref "C7") (pin "2") (pinfunction "2_2") (pintype "passive"))
      (node (ref "C8") (pin "2") (pinfunction "2_2") (pintype "passive"))
      (node (ref "CR1") (pin "2") (pinfunction "2_2") (pintype "passive"))
      (node (ref "DISPLAY") (pin "2") (pinfunction "2_2") (pintype "passive"))
      (node (ref "DRV_X") (pin "1") (pinfunction "GND_1") (pintype "power_in"))
      (node (ref "DRV_X") (pin "7") (pinfunction "GND_7") (pintype "power_in"))
      (node (ref "DRV_Z") (pin "1") (pinfunction "GND_1") (pintype "power_in"))
      (node (ref "DRV_Z") (pin "7") (pinfunction "GND_7") (pintype "power_in"))
      (node (ref "GND") (pin "1") (pinfunction "1_1") (pintype "passive"))
      (node (ref "GND") (pin "2") (pinfunction "2_2") (pintype "passive"))
      (node (ref "GND") (pin "3") (pinfunction "3_3") (pintype "passive"))
      (node (ref "GND") (pin "4") (pinfunction "4_4") (pintype "passive"))
      (node (ref "GND") (pin "5") (pinfunction "5_5") (pintype "passive"))
      (node (ref "J10") (pin "19") (pinfunction "19_19") (pintype "passive"))
      (node (ref "J10") (pin "20") (pinfunction "20_20") (pintype "passive"))
      (node (ref "LIM") (pin "2") (pinfunction "2_2") (pintype "passive"))
      (node (ref "LIM") (pin "4") (pinfunction "4_4") (pintype "passive"))
      (node (ref "R23") (pin "1") (pinfunction "1_1") (pintype "passive"))
      (node (ref "R25") (pin "1") (pinfunction "1_1") (pintype "passive"))
      (node (ref "S1") (pin "C") (pinfunction "C_C") (pintype "bidirectional"))
      (node (ref "S1") (pin "SW-") (pinfunction "SW-_SW-") (pintype "bidirectional"))
      (node (ref "SEN0") (pin "3") (pinfunction "S_3") (pintype "passive"))
      (node (ref "SEN0") (pin "5") (pinfunction "S_5") (pintype "passive"))
      (node (ref "SEN0") (pin "7") (pinfunction "S_7") (pintype "passive"))
      (node (ref "SEN0-S") (pin "3") (pinfunction "3_3") (pintype "passive"))
      (node (ref "SEN0-S") (pin "5") (pinfunction "5_5") (pintype "passive"))
      (node (ref "SEN0-S") (pin "7") (pinfunction "7_7") (pintype "passive"))
      (node (ref "SEN1") (pin "3") (pinfunction "S_3") (pintype "passive"))
      (node (ref "SEN1") (pin "5") (pinfunction "S_5") (pintype "passive"))
      (node (ref "SEN1") (pin "7") (pinfunction "S_7") (pintype "passive"))
      (node (ref "SEN1-S") (pin "3") (pinfunction "3_3") (pintype "passive"))
      (node (ref "SEN1-S") (pin "5") (pinfunction "5_5") (pintype "passive"))
      (node (ref "SEN1-S") (pin "7") (pinfunction "7_7") (pintype "passive"))
      (node (ref "SEN2") (pin "3") (pinfunction "S_3") (pintype "passive"))
      (node (ref "SEN2") (pin "5") (pinfunction "S_5") (pintype "passive"))
      (node (ref "SEN2") (pin "7") (pinfunction "S_7") (pintype "passive"))
      (node (ref "SEN2-S") (pin "3") (pinfunction "3_3") (pintype "passive"))
      (node (ref "SEN2-S") (pin "5") (pinfunction "5_5") (pintype "passive"))
      (node (ref "SEN2-S") (pin "7") (pinfunction "7_7") (pintype "passive"))
      (node (ref "SEN3") (pin "3") (pinfunction "S_3") (pintype "passive"))
      (node (ref "SEN3") (pin "5") (pinfunction "S_5") (pintype "passive"))
      (node (ref "SEN3") (pin "7") (pinfunction "S_7") (pintype "passive"))
      (node (ref "SEN3-S") (pin "3") (pinfunction "3_3") (pintype "passive"))
      (node (ref "SEN3-S") (pin "5") (pinfunction "5_5") (pintype "passive"))
      (node (ref "SEN3-S") (pin "7") (pinfunction "7_7") (pintype "passive"))
      (node (ref "U$1") (pin "GND1") (pinfunction "GND1_GND1") (pintype "power_in"))
      (node (ref "U$1") (pin "GND2") (pinfunction "GND2_GND2") (pintype "power_in"))
      (node (ref "U1") (pin "7") (pinfunction "GND_7") (pintype "power_in"))
      (node (ref "U1") (pin "EPAD") (pinfunction "EPAD_EPAD") (pintype "passive"))
    )
    (net (code "38") (name "Net-(C7-Pad1)") (class "Default")
      (node (ref "C7") (pin "1") (pinfunction "1_1") (pintype "passive"))
      (node (ref "R24") (pin "1") (pinfunction "1_1") (pintype "passive"))
    )
    (net (code "39") (name "Net-(DRV_X-DIR)") (class "Default")
      (node (ref "DRV_X") (pin "9") (pinfunction "DIR_9") (pintype "input"))
      (node (ref "J9") (pin "3") (pinfunction "3_3") (pintype "passive"))
      (node (ref "J9") (pin "4") (pinfunction "4_4") (pintype "passive"))
      (node (ref "U$1") (pin "14") (pinfunction "14/A0_14") (pintype "bidirectional"))
    )
    (net (code "40") (name "Net-(DRV_X-M1A)") (class "Default")
      (node (ref "DRV_X") (pin "5") (pinfunction "M1A_5") (pintype "output"))
      (node (ref "J6") (pin "3") (pinfunction "3_3") (pintype "passive"))
    )
    (net (code "41") (name "Net-(DRV_X-M1B)") (class "Default")
      (node (ref "DRV_X") (pin "4") (pinfunction "M1B_4") (pintype "output"))
      (node (ref "J6") (pin "2") (pinfunction "2_2") (pintype "passive"))
    )
    (net (code "42") (name "Net-(DRV_X-M2A)") (class "Default")
      (node (ref "DRV_X") (pin "6") (pinfunction "M2A_6") (pintype "output"))
      (node (ref "J6") (pin "4") (pinfunction "4_4") (pintype "passive"))
    )
    (net (code "43") (name "Net-(DRV_X-M2B)") (class "Default")
      (node (ref "DRV_X") (pin "3") (pinfunction "M2B_3") (pintype "output"))
      (node (ref "J6") (pin "1") (pinfunction "1_1") (pintype "passive"))
    )
    (net (code "44") (name "Net-(DRV_X-STEP)") (class "Default")
      (node (ref "DRV_X") (pin "10") (pinfunction "STEP_10") (pintype "input"))
      (node (ref "J9") (pin "5") (pinfunction "5_5") (pintype "passive"))
      (node (ref "J9") (pin "6") (pinfunction "6_6") (pintype "passive"))
      (node (ref "U$1") (pin "15") (pinfunction "15/A1_15") (pintype "bidirectional"))
    )
    (net (code "45") (name "Net-(DRV_X-~{EN})") (class "Default")
      (node (ref "DRV_X") (pin "16") (pinfunction "~{EN}_16") (pintype "input"))
      (node (ref "J9") (pin "11") (pinfunction "11_11") (pintype "passive"))
      (node (ref "J9") (pin "12") (pinfunction "12_12") (pintype "passive"))
      (node (ref "U$1") (pin "18") (pinfunction "18/A4/SDA0_18") (pintype "bidirectional"))
    )
    (net (code "46") (name "Net-(DRV_Z-M1A)") (class "Default")
      (node (ref "DRV_Z") (pin "5") (pinfunction "M1A_5") (pintype "output"))
      (node (ref "J7") (pin "3") (pinfunction "3_3") (pintype "passive"))
    )
    (net (code "47") (name "Net-(DRV_Z-M1B)") (class "Default")
      (node (ref "DRV_Z") (pin "4") (pinfunction "M1B_4") (pintype "output"))
      (node (ref "J7") (pin "2") (pinfunction "2_2") (pintype "passive"))
    )
    (net (code "48") (name "Net-(DRV_Z-M2A)") (class "Default")
      (node (ref "DRV_Z") (pin "6") (pinfunction "M2A_6") (pintype "output"))
      (node (ref "J7") (pin "4") (pinfunction "4_4") (pintype "passive"))
    )
    (net (code "49") (name "Net-(DRV_Z-M2B)") (class "Default")
      (node (ref "DRV_Z") (pin "3") (pinfunction "M2B_3") (pintype "output"))
      (node (ref "J7") (pin "1") (pinfunction "1_1") (pintype "passive"))
    )
    (net (code "50") (name "Net-(J1-Pad1)") (class "Default")
      (node (ref "J1") (pin "1") (pinfunction "1_1") (pintype "passive"))
      (node (ref "J1") (pin "2") (pinfunction "2_2") (pintype "passive"))
      (node (ref "U$1") (pin "AGND") (pinfunction "AGND_AGND") (pintype "power_in"))
    )
    (net (code "51") (name "Net-(J10-Pad5)") (class "Default")
      (node (ref "J10") (pin "5") (pinfunction "5_5") (pintype "passive"))
      (node (ref "J10") (pin "6") (pinfunction "6_6") (pintype "passive"))
      (node (ref "R9") (pin "2") (pinfunction "2_2") (pintype "passive"))
      (node (ref "U$1") (pin "35") (pinfunction "35_35") (pintype "bidirectional"))
    )
    (net (code "52") (name "Net-(J10-Pad10)") (class "Default")
      (node (ref "J10") (pin "10") (pinfunction "10_10") (pintype "passive"))
      (node (ref "J10") (pin "9") (pinfunction "9_9") (pintype "passive"))
      (node (ref "U$1") (pin "37") (pinfunction "37_37") (pintype "bidirectional"))
    )
    (net (code "53") (name "Net-(J12-Pad1)") (class "Default")
      (node (ref "J12") (pin "1") (pinfunction "1_1") (pintype "passive"))
      (node (ref "J12") (pin "2") (pinfunction "2_2") (pintype "passive"))
      (node (ref "U$1") (pin "28") (pinfunction "28_28") (pintype "bidirectional"))
    )
    (net (code "54") (name "Net-(J12-Pad3)") (class "Default")
      (node (ref "J12") (pin "3") (pinfunction "3_3") (pintype "passive"))
      (node (ref "J12") (pin "4") (pinfunction "4_4") (pintype "passive"))
      (node (ref "U$1") (pin "29") (pinfunction "29_29") (pintype "bidirectional"))
    )
    (net (code "55") (name "Net-(U$1-0{slash}RX1)") (class "Default")
      (node (ref "J8") (pin "1") (pinfunction "1_1") (pintype "passive"))
      (node (ref "J8") (pin "2") (pinfunction "2_2") (pintype "passive"))
      (node (ref "U$1") (pin "0") (pinfunction "0/RX1_0") (pintype "bidirectional"))
    )
    (net (code "56") (name "Net-(U$1-7{slash}RX3)") (class "Default")
      (node (ref "J8") (pin "15") (pinfunction "15_15") (pintype "passive"))
      (node (ref "J8") (pin "16") (pinfunction "16_16") (pintype "passive"))
      (node (ref "U$1") (pin "7") (pinfunction "7/RX3_7") (pintype "bidirectional"))
    )
    (net (code "57") (name "Net-(U$1-8{slash}TX3)") (class "Default")
      (node (ref "J8") (pin "17") (pinfunction "17_17") (pintype "passive"))
      (node (ref "J8") (pin "18") (pinfunction "18_18") (pintype "passive"))
      (node (ref "U$1") (pin "8") (pinfunction "8/TX3_8") (pintype "bidirectional"))
    )
    (net (code "58") (name "Net-(U$1-9*{slash}RX2)") (class "Default")
      (node (ref "J8") (pin "19") (pinfunction "19_19") (pintype "passive"))
      (node (ref "J8") (pin "20") (pinfunction "20_20") (pintype "passive"))
      (node (ref "U$1") (pin "9") (pinfunction "9*/RX2_9") (pintype "bidirectional"))
    )
    (net (code "59") (name "Net-(U$1-17{slash}A3)") (class "Default")
      (node (ref "J9") (pin "10") (pinfunction "10_10") (pintype "passive"))
      (node (ref "J9") (pin "9") (pinfunction "9_9") (pintype "passive"))
      (node (ref "R8") (pin "1") (pinfunction "1_1") (pintype "passive"))
      (node (ref "U$1") (pin "17") (pinfunction "17/A3_17") (pintype "bidirectional"))
    )
    (net (code "60") (name "Net-(U$1-19{slash}A5{slash}SCL0)") (class "Default")
      (node (ref "J9") (pin "13") (pinfunction "13_13") (pintype "passive"))
      (node (ref "J9") (pin "14") (pinfunction "14_14") (pintype "passive"))
      (node (ref "U$1") (pin "19") (pinfunction "19/A5/SCL0_19") (pintype "bidirectional"))
    )
    (net (code "61") (name "Net-(U$1-20{slash}A6)") (class "Default")
      (node (ref "J9") (pin "15") (pinfunction "15_15") (pintype "passive"))
      (node (ref "J9") (pin "16") (pinfunction "16_16") (pintype "passive"))
      (node (ref "U$1") (pin "20") (pinfunction "20/A6_20") (pintype "bidirectional"))
    )
    (net (code "62") (name "Net-(U$1-23{slash}A9)") (class "Default")
      (node (ref "J2") (pin "1") (pinfunction "1_1") (pintype "passive"))
      (node (ref "J2") (pin "2") (pinfunction "2_2") (pintype "passive"))
      (node (ref "U$1") (pin "23") (pinfunction "23/A9_23") (pintype "bidirectional"))
    )
    (net (code "63") (name "Net-(U$1-24{slash}A10)") (class "Default")
      (node (ref "J11") (pin "1") (pinfunction "1_1") (pintype "passive"))
      (node (ref "J11") (pin "2") (pinfunction "2_2") (pintype "passive"))
      (node (ref "U$1") (pin "24") (pinfunction "24/A10_24") (pintype "bidirectional"))
    )
    (net (code "64") (name "Net-(U$1-25{slash}A11)") (class "Default")
      (node (ref "J11") (pin "3") (pinfunction "3_3") (pintype "passive"))
      (node (ref "J11") (pin "4") (pinfunction "4_4") (pintype "passive"))
      (node (ref "U$1") (pin "25") (pinfunction "25/A11_25") (pintype "bidirectional"))
    )
    (net (code "65") (name "Net-(U$1-38{slash}A14)") (class "Default")
      (node (ref "J10") (pin "11") (pinfunction "11_11") (pintype "passive"))
      (node (ref "J10") (pin "12") (pinfunction "12_12") (pintype "passive"))
      (node (ref "U$1") (pin "38") (pinfunction "38/A14_38") (pintype "bidirectional"))
    )
    (net (code "66") (name "Net-(U1-BOOT)") (class "Default")
      (node (ref "C9") (pin "1") (pinfunction "1_1") (pintype "passive"))
      (node (ref "U1") (pin "1") (pinfunction "BOOT_1") (pintype "output"))
    )
    (net (code "67") (name "Net-(U1-COMP)") (class "Default")
      (node (ref "C8") (pin "1") (pinfunction "1_1") (pintype "passive"))
      (node (ref "R24") (pin "2") (pinfunction "2_2") (pintype "passive"))
      (node (ref "U1") (pin "6") (pinfunction "COMP_6") (pintype "output"))
    )
    (net (code "68") (name "Net-(U1-FB)") (class "Default")
      (node (ref "R25") (pin "2") (pinfunction "2_2") (pintype "passive"))
      (node (ref "R26") (pin "1") (pinfunction "1_1") (pintype "passive"))
      (node (ref "U1") (pin "5") (pinfunction "FB_5") (pintype "input"))
    )
    (net (code "69") (name "Net-(U1-RT{slash}CLK)") (class "Default")
      (node (ref "R23") (pin "2") (pinfunction "2_2") (pintype "passive"))
      (node (ref "U1") (pin "4") (pinfunction "RT/CLK_4") (pintype "input"))
    )
    (net (code "70") (name "Net-(U1-SW)") (class "Default")
      (node (ref "C9") (pin "2") (pinfunction "2_2") (pintype "passive"))
      (node (ref "CR1") (pin "1") (pinfunction "1_1") (pintype "passive"))
      (node (ref "L1") (pin "1") (pinfunction "1_1") (pintype "passive"))
      (node (ref "U1") (pin "8") (pinfunction "SW_8") (pintype "input"))
    )
    (net (code "71") (name "unconnected-(DISPLAY-Pad7)") (class "Default")
      (node (ref "DISPLAY") (pin "7") (pinfunction "7_7") (pintype "passive"))
    )
    (net (code "72") (name "unconnected-(DISPLAY-Pad8)") (class "Default")
      (node (ref "DISPLAY") (pin "8") (pinfunction "8_8") (pintype "passive"))
    )
    (net (code "73") (name "unconnected-(DRV_X-CLK-Pad11)") (class "Default")
      (node (ref "DRV_X") (pin "11") (pinfunction "CLK_11") (pintype "bidirectional"))
    )
    (net (code "74") (name "unconnected-(DRV_X-DIAG-Pad18)") (class "Default")
      (node (ref "DRV_X") (pin "18") (pinfunction "DIAG_18") (pintype "output"))
    )
    (net (code "75") (name "unconnected-(DRV_X-INDEX-Pad17)") (class "Default")
      (node (ref "DRV_X") (pin "17") (pinfunction "INDEX_17") (pintype "output"))
    )
    (net (code "76") (name "unconnected-(DRV_X-MS1-Pad15)") (class "Default")
      (node (ref "DRV_X") (pin "15") (pinfunction "MS1_15") (pintype "input"))
    )
    (net (code "77") (name "unconnected-(DRV_X-MS2-Pad14)") (class "Default")
      (node (ref "DRV_X") (pin "14") (pinfunction "MS2_14") (pintype "input"))
    )
    (net (code "78") (name "unconnected-(DRV_X-TX-Pad12)") (class "Default")
      (node (ref "DRV_X") (pin "12") (pinfunction "TX_12") (pintype "bidirectional"))
    )
    (net (code "79") (name "unconnected-(DRV_Z-CLK-Pad11)") (class "Default")
      (node (ref "DRV_Z") (pin "11") (pinfunction "CLK_11") (pintype "bidirectional"))
    )
    (net (code "80") (name "unconnected-(DRV_Z-DIAG-Pad18)") (class "Default")
      (node (ref "DRV_Z") (pin "18") (pinfunction "DIAG_18") (pintype "output"))
    )
    (net (code "81") (name "unconnected-(DRV_Z-INDEX-Pad17)") (class "Default")
      (node (ref "DRV_Z") (pin "17") (pinfunction "INDEX_17") (pintype "output"))
    )
    (net (code "82") (name "unconnected-(DRV_Z-MS1-Pad15)") (class "Default")
      (node (ref "DRV_Z") (pin "15") (pinfunction "MS1_15") (pintype "input"))
    )
    (net (code "83") (name "unconnected-(DRV_Z-MS2-Pad14)") (class "Default")
      (node (ref "DRV_Z") (pin "14") (pinfunction "MS2_14") (pintype "input"))
    )
    (net (code "84") (name "unconnected-(DRV_Z-TX-Pad12)") (class "Default")
      (node (ref "DRV_Z") (pin "12") (pinfunction "TX_12") (pintype "bidirectional"))
    )
    (net (code "85") (name "unconnected-(U1-EN-Pad3)") (class "Default")
      (node (ref "U1") (pin "3") (pinfunction "EN_3") (pintype "input"))
    )
  )
)
